# design.net
KiCad netlist of a schematic drawn in Altium Designer
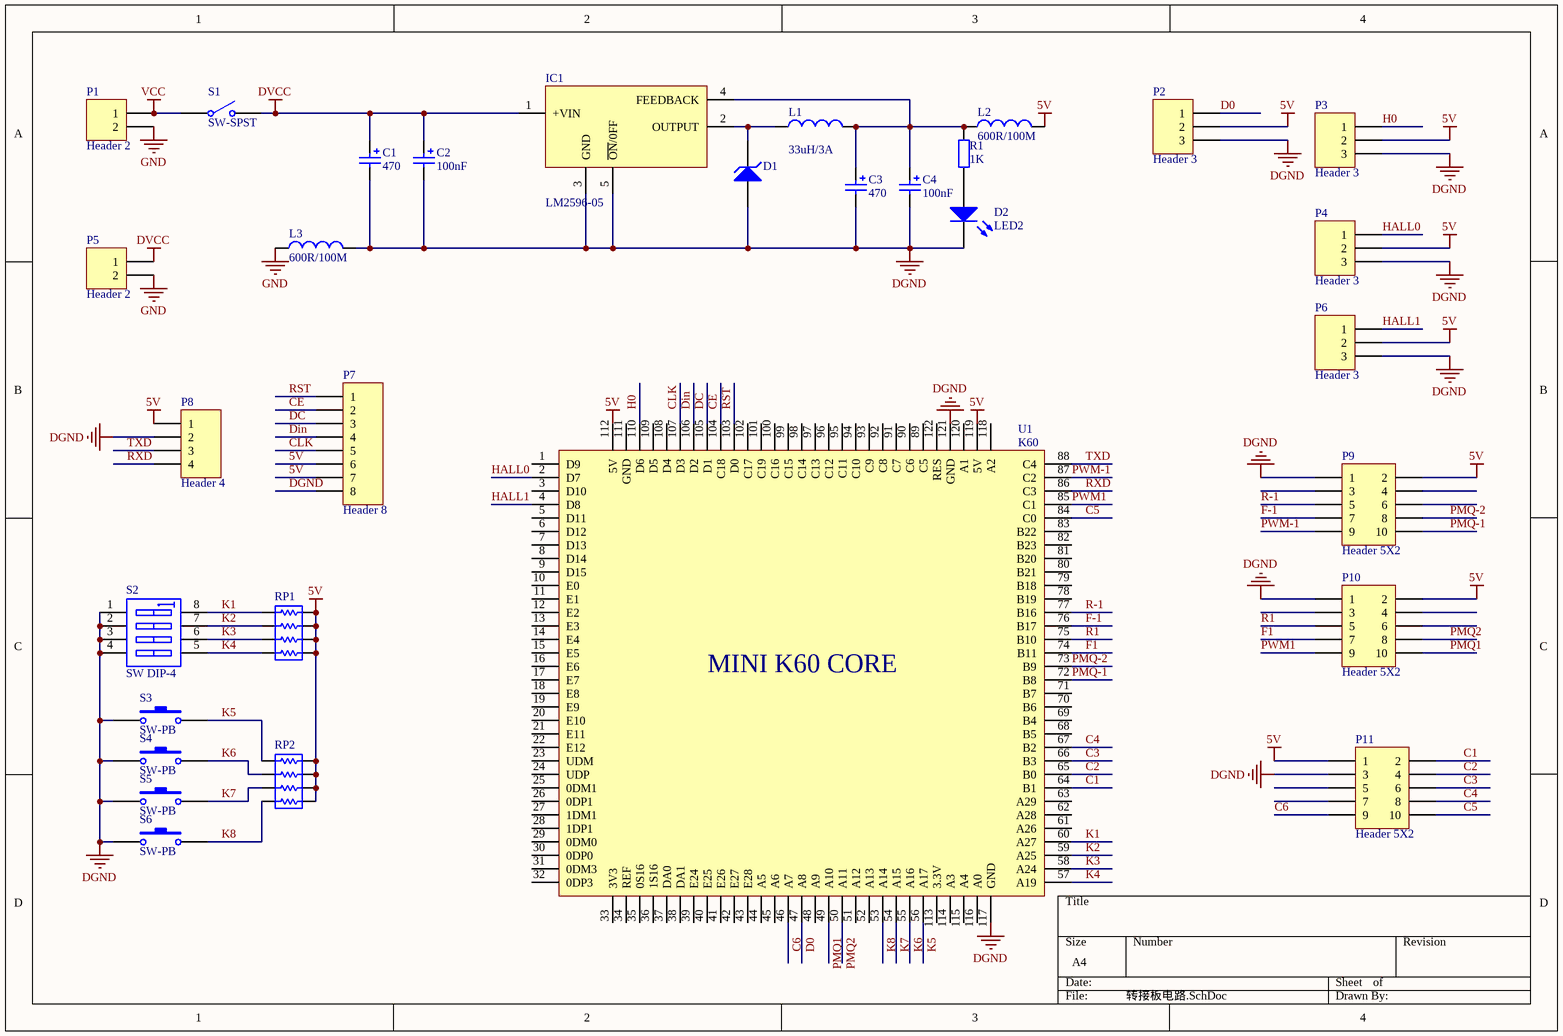
[diagram p0: 转接板电路.SchDoc]

(export (version "E")
  (design (tool "Eeschema 10.0.6"))
  (components
    (comp (ref "C1")
      (value "470")
      (footprint "ccc")
      (description "Polarized Capacitor (Axial)")
      (fields (field (name "PUBLISHER") "Altium Limited"))
      (libsource (lib "Miscellaneous Devices") (part "Cap Pol2"))
    )
    (comp (ref "C2")
      (value "100nF")
      (footprint "C0805")
      (description "Polarized Capacitor (Axial)")
      (fields (field (name "PUBLISHER") "Altium Limited"))
      (libsource (lib "Miscellaneous Devices") (part "Cap Pol2"))
    )
    (comp (ref "C3")
      (value "470")
      (footprint "ccc")
      (description "Polarized Capacitor (Axial)")
      (fields (field (name "PUBLISHER") "Altium Limited"))
      (libsource (lib "Miscellaneous Devices") (part "Cap Pol2"))
    )
    (comp (ref "C4")
      (value "100nF")
      (footprint "C0805")
      (description "Polarized Capacitor (Axial)")
      (fields (field (name "PUBLISHER") "Altium Limited"))
      (libsource (lib "Miscellaneous Devices") (part "Cap Pol2"))
    )
    (comp (ref "D1")
      (value "D Zener")
      (footprint "D1810")
      (description "Zener Diode")
      (fields (field (name "PUBLISHER") "Altium Limited"))
      (libsource (lib "Miscellaneous Devices") (part "D Zener"))
    )
    (comp (ref "D2")
      (value "LED2")
      (footprint "D0805")
      (description "Typical RED, GREEN, YELLOW, AMBER GaAs LED")
      (fields (field (name "PUBLISHER") "Altium Limited"))
      (libsource (lib "Miscellaneous Devices") (part "LED2"))
    )
    (comp (ref "IC1")
      (value "LM2596-05")
      (footprint "TO-263-5")
      (libsource (lib "飞思卡尔元件库") (part "LM2596-05"))
    )
    (comp (ref "L1")
      (value "33uH/3A")
      (footprint "L-12*12MM-S")
      (description "Inductor")
      (fields (field (name "PUBLISHER") "Altium Limited"))
      (libsource (lib "Miscellaneous Devices") (part "Inductor"))
    )
    (comp (ref "L2")
      (value "600R/100M")
      (footprint "L1206")
      (description "Inductor")
      (fields (field (name "PUBLISHER") "Altium Limited"))
      (libsource (lib "Miscellaneous Devices") (part "Inductor"))
    )
    (comp (ref "L3")
      (value "600R/100M")
      (footprint "L1206")
      (description "Inductor")
      (fields (field (name "PUBLISHER") "Altium Limited"))
      (libsource (lib "Miscellaneous Devices") (part "Inductor"))
    )
    (comp (ref "P1")
      (value "Header 2")
      (footprint "SIP2-1")
      (description "Header, 2-Pin")
      (fields (field (name "PUBLISHER") "Altium Limited"))
      (libsource (lib "Miscellaneous Connectors") (part "Header 2"))
    )
    (comp (ref "P2")
      (value "Header 3")
      (footprint "SIP3")
      (description "Header, 3-Pin")
      (fields (field (name "PUBLISHER") "Altium Limited"))
      (libsource (lib "Miscellaneous Connectors") (part "Header 3"))
    )
    (comp (ref "P3")
      (value "Header 3")
      (footprint "SIP3")
      (description "Header, 3-Pin")
      (fields (field (name "PUBLISHER") "Altium Limited"))
      (libsource (lib "Miscellaneous Connectors") (part "Header 3"))
    )
    (comp (ref "P4")
      (value "Header 3")
      (footprint "SIP3")
      (description "Header, 3-Pin")
      (fields (field (name "PUBLISHER") "Altium Limited"))
      (libsource (lib "Miscellaneous Connectors") (part "Header 3"))
    )
    (comp (ref "P5")
      (value "Header 2")
      (footprint "SIP2-1")
      (description "Header, 2-Pin")
      (fields (field (name "PUBLISHER") "Altium Limited"))
      (libsource (lib "Miscellaneous Connectors") (part "Header 2"))
    )
    (comp (ref "P6")
      (value "Header 3")
      (footprint "SIP3")
      (description "Header, 3-Pin")
      (fields (field (name "PUBLISHER") "Altium Limited"))
      (libsource (lib "Miscellaneous Connectors") (part "Header 3"))
    )
    (comp (ref "P7")
      (value "Header 8")
      (footprint "SIP8")
      (description "Header, 8-Pin")
      (fields (field (name "PUBLISHER") "Altium Limited"))
      (libsource (lib "Miscellaneous Connectors") (part "Header 8"))
    )
    (comp (ref "P8")
      (value "Header 4")
      (footprint "SIP4")
      (description "Header, 4-Pin")
      (fields (field (name "PUBLISHER") "Altium Limited"))
      (libsource (lib "Miscellaneous Connectors") (part "Header 4"))
    )
    (comp (ref "P9")
      (value "Header 5X2")
      (footprint "SIP10")
      (description "Header, 5-Pin, Dual row")
      (fields (field (name "PUBLISHER") "Altium Limited"))
      (libsource (lib "Miscellaneous Connectors") (part "Header 5X2"))
    )
    (comp (ref "P10")
      (value "Header 5X2")
      (footprint "SIP10")
      (description "Header, 5-Pin, Dual row")
      (fields (field (name "PUBLISHER") "Altium Limited"))
      (libsource (lib "Miscellaneous Connectors") (part "Header 5X2"))
    )
    (comp (ref "P11")
      (value "Header 5X2")
      (footprint "SIP10")
      (description "Header, 5-Pin, Dual row")
      (fields (field (name "PUBLISHER") "Altium Limited"))
      (libsource (lib "Miscellaneous Connectors") (part "Header 5X2"))
    )
    (comp (ref "R1")
      (value "1K")
      (footprint "R0805")
      (description "Resistor")
      (fields (field (name "Comment") "Res2") (field (name "PUBLISHER") "Altium Limited"))
      (libsource (lib "Miscellaneous Devices") (part "Res2"))
    )
    (comp (ref "RP1")
      (value "R  PAIZU")
      (footprint "8P4R-0805")
      (fields (field (name "PUBLISHER") "Altium Limited"))
      (libsource (lib "飞思卡尔元件库") (part "R  PAIZU"))
    )
    (comp (ref "RP2")
      (value "R  PAIZU")
      (footprint "8P4R-0805")
      (fields (field (name "PUBLISHER") "Altium Limited"))
      (libsource (lib "飞思卡尔元件库") (part "R  PAIZU"))
    )
    (comp (ref "S1")
      (value "SW-SPST")
      (footprint "PCBComponent_1")
      (description "Single-Pole, Single-Throw Switch")
      (fields (field (name "PUBLISHER") "Altium Limited"))
      (libsource (lib "Miscellaneous Devices") (part "SW-SPST"))
    )
    (comp (ref "S2")
      (value "SW DIP-4")
      (footprint "BM-SW-4")
      (description "DIP Switch, 4 Position, SPST")
      (fields (field (name "PUBLISHER") "Altium Limited"))
      (libsource (lib "Miscellaneous Devices") (part "SW DIP-4"))
    )
    (comp (ref "S3")
      (value "SW-PB")
      (footprint "SW-SMD1")
      (description "Switch")
      (fields (field (name "PUBLISHER") "Altium Limited"))
      (libsource (lib "Miscellaneous Devices") (part "SW-PB"))
    )
    (comp (ref "S4")
      (value "SW-PB")
      (footprint "SW-SMD1")
      (description "Switch")
      (fields (field (name "PUBLISHER") "Altium Limited"))
      (libsource (lib "Miscellaneous Devices") (part "SW-PB"))
    )
    (comp (ref "S5")
      (value "SW-PB")
      (footprint "SW-SMD1")
      (description "Switch")
      (fields (field (name "PUBLISHER") "Altium Limited"))
      (libsource (lib "Miscellaneous Devices") (part "SW-PB"))
    )
    (comp (ref "S6")
      (value "SW-PB")
      (footprint "SW-SMD1")
      (description "Switch")
      (fields (field (name "PUBLISHER") "Altium Limited"))
      (libsource (lib "Miscellaneous Devices") (part "SW-PB"))
    )
    (comp (ref "U1") (value "K60") (footprint "K60-MK") (libsource (lib "飞思卡尔元件库") (part "K60")))
  )
  (nets
    (net (code "1") (name "/C1") (class "Default")
      (node (ref "P11") (pin "2") (pinfunction "2_2") (pintype "passive"))
      (node (ref "U1") (pin "64") (pinfunction "B1_64") (pintype "passive"))
    )
    (net (code "2") (name "/C2") (class "Default")
      (node (ref "P11") (pin "4") (pinfunction "4_4") (pintype "passive"))
      (node (ref "U1") (pin "65") (pinfunction "B0_65") (pintype "passive"))
    )
    (net (code "3") (name "/C3") (class "Default")
      (node (ref "P11") (pin "6") (pinfunction "6_6") (pintype "passive"))
      (node (ref "U1") (pin "66") (pinfunction "B3_66") (pintype "passive"))
    )
    (net (code "4") (name "/C4") (class "Default")
      (node (ref "P11") (pin "8") (pinfunction "8_8") (pintype "passive"))
      (node (ref "U1") (pin "67") (pinfunction "B2_67") (pintype "passive"))
    )
    (net (code "5") (name "/C5") (class "Default")
      (node (ref "P11") (pin "10") (pinfunction "10_10") (pintype "passive"))
      (node (ref "U1") (pin "84") (pinfunction "C0_84") (pintype "passive"))
    )
    (net (code "6") (name "/C6") (class "Default")
      (node (ref "P11") (pin "9") (pinfunction "9_9") (pintype "passive"))
      (node (ref "U1") (pin "46") (pinfunction "A7_46") (pintype "passive"))
    )
    (net (code "7") (name "/CE") (class "Default")
      (node (ref "P7") (pin "2") (pinfunction "2_2") (pintype "passive"))
      (node (ref "U1") (pin "104") (pinfunction "C18_104") (pintype "passive"))
    )
    (net (code "8") (name "/CLK") (class "Default")
      (node (ref "P7") (pin "5") (pinfunction "5_5") (pintype "passive"))
      (node (ref "U1") (pin "107") (pinfunction "D3_107") (pintype "passive"))
    )
    (net (code "9") (name "/D0") (class "Default")
      (node (ref "P2") (pin "1") (pinfunction "1_1") (pintype "passive"))
      (node (ref "U1") (pin "47") (pinfunction "A8_47") (pintype "passive"))
    )
    (net (code "10") (name "/DC") (class "Default")
      (node (ref "P7") (pin "3") (pinfunction "3_3") (pintype "passive"))
      (node (ref "U1") (pin "105") (pinfunction "D1_105") (pintype "passive"))
    )
    (net (code "11") (name "/Din") (class "Default")
      (node (ref "P7") (pin "4") (pinfunction "4_4") (pintype "passive"))
      (node (ref "U1") (pin "106") (pinfunction "D2_106") (pintype "passive"))
    )
    (net (code "12") (name "/F-1") (class "Default")
      (node (ref "P9") (pin "7") (pinfunction "7_7") (pintype "passive"))
      (node (ref "U1") (pin "76") (pinfunction "B17_76") (pintype "passive"))
    )
    (net (code "13") (name "/F1") (class "Default")
      (node (ref "P10") (pin "7") (pinfunction "7_7") (pintype "passive"))
      (node (ref "U1") (pin "74") (pinfunction "B11_74") (pintype "passive"))
    )
    (net (code "14") (name "/H0") (class "Default")
      (node (ref "P3") (pin "1") (pinfunction "1_1") (pintype "passive"))
      (node (ref "U1") (pin "110") (pinfunction "D6_110") (pintype "passive"))
    )
    (net (code "15") (name "/HALL0") (class "Default")
      (node (ref "P4") (pin "1") (pinfunction "1_1") (pintype "passive"))
      (node (ref "U1") (pin "2") (pinfunction "D7_2") (pintype "passive"))
    )
    (net (code "16") (name "/HALL1") (class "Default")
      (node (ref "P6") (pin "1") (pinfunction "1_1") (pintype "passive"))
      (node (ref "U1") (pin "4") (pinfunction "D8_4") (pintype "passive"))
    )
    (net (code "17") (name "/K1") (class "Default")
      (node (ref "RP1") (pin "1") (pinfunction "1_1") (pintype "passive"))
      (node (ref "S2") (pin "8") (pinfunction "B1_8") (pintype "passive"))
      (node (ref "U1") (pin "60") (pinfunction "A27_60") (pintype "passive"))
    )
    (net (code "18") (name "/K2") (class "Default")
      (node (ref "RP1") (pin "2") (pinfunction "2_2") (pintype "passive"))
      (node (ref "S2") (pin "7") (pinfunction "B2_7") (pintype "passive"))
      (node (ref "U1") (pin "59") (pinfunction "A25_59") (pintype "passive"))
    )
    (net (code "19") (name "/K3") (class "Default")
      (node (ref "RP1") (pin "3") (pinfunction "3_3") (pintype "passive"))
      (node (ref "S2") (pin "6") (pinfunction "B3_6") (pintype "passive"))
      (node (ref "U1") (pin "58") (pinfunction "A24_58") (pintype "passive"))
    )
    (net (code "20") (name "/K4") (class "Default")
      (node (ref "RP1") (pin "4") (pinfunction "4_4") (pintype "passive"))
      (node (ref "S2") (pin "5") (pinfunction "B4_5") (pintype "passive"))
      (node (ref "U1") (pin "57") (pinfunction "A19_57") (pintype "passive"))
    )
    (net (code "21") (name "/K5") (class "Default")
      (node (ref "RP2") (pin "1") (pinfunction "1_1") (pintype "passive"))
      (node (ref "S3") (pin "2") (pinfunction "2_2") (pintype "passive"))
      (node (ref "U1") (pin "56") (pinfunction "A17_56") (pintype "passive"))
    )
    (net (code "22") (name "/K6") (class "Default")
      (node (ref "RP2") (pin "2") (pinfunction "2_2") (pintype "passive"))
      (node (ref "S4") (pin "2") (pinfunction "2_2") (pintype "passive"))
      (node (ref "U1") (pin "55") (pinfunction "A16_55") (pintype "passive"))
    )
    (net (code "23") (name "/K7") (class "Default")
      (node (ref "RP2") (pin "3") (pinfunction "3_3") (pintype "passive"))
      (node (ref "S5") (pin "2") (pinfunction "2_2") (pintype "passive"))
      (node (ref "U1") (pin "54") (pinfunction "A15_54") (pintype "passive"))
    )
    (net (code "24") (name "/K8") (class "Default")
      (node (ref "RP2") (pin "4") (pinfunction "4_4") (pintype "passive"))
      (node (ref "S6") (pin "2") (pinfunction "2_2") (pintype "passive"))
      (node (ref "U1") (pin "53") (pinfunction "A14_53") (pintype "passive"))
    )
    (net (code "25") (name "/PMQ-1") (class "Default")
      (node (ref "P9") (pin "10") (pinfunction "10_10") (pintype "passive"))
      (node (ref "U1") (pin "72") (pinfunction "B8_72") (pintype "passive"))
    )
    (net (code "26") (name "/PMQ-2") (class "Default")
      (node (ref "P9") (pin "8") (pinfunction "8_8") (pintype "passive"))
      (node (ref "U1") (pin "73") (pinfunction "B9_73") (pintype "passive"))
    )
    (net (code "27") (name "/PMQ1") (class "Default")
      (node (ref "P10") (pin "10") (pinfunction "10_10") (pintype "passive"))
      (node (ref "U1") (pin "49") (pinfunction "A10_49") (pintype "passive"))
    )
    (net (code "28") (name "/PMQ2") (class "Default")
      (node (ref "P10") (pin "8") (pinfunction "8_8") (pintype "passive"))
      (node (ref "U1") (pin "50") (pinfunction "A11_50") (pintype "passive"))
    )
    (net (code "29") (name "/PWM-1") (class "Default")
      (node (ref "P9") (pin "9") (pinfunction "9_9") (pintype "passive"))
      (node (ref "U1") (pin "87") (pinfunction "C2_87") (pintype "passive"))
    )
    (net (code "30") (name "/PWM1") (class "Default")
      (node (ref "P10") (pin "9") (pinfunction "9_9") (pintype "passive"))
      (node (ref "U1") (pin "85") (pinfunction "C1_85") (pintype "passive"))
    )
    (net (code "31") (name "/R-1") (class "Default")
      (node (ref "P9") (pin "5") (pinfunction "5_5") (pintype "passive"))
      (node (ref "U1") (pin "77") (pinfunction "B16_77") (pintype "passive"))
    )
    (net (code "32") (name "/R1") (class "Default")
      (node (ref "P10") (pin "5") (pinfunction "5_5") (pintype "passive"))
      (node (ref "U1") (pin "75") (pinfunction "B10_75") (pintype "passive"))
    )
    (net (code "33") (name "/RST") (class "Default")
      (node (ref "P7") (pin "1") (pinfunction "1_1") (pintype "passive"))
      (node (ref "U1") (pin "103") (pinfunction "D0_103") (pintype "passive"))
    )
    (net (code "34") (name "/RXD") (class "Default")
      (node (ref "P8") (pin "4") (pinfunction "4_4") (pintype "passive"))
      (node (ref "U1") (pin "86") (pinfunction "C3_86") (pintype "passive"))
    )
    (net (code "35") (name "/TXD") (class "Default")
      (node (ref "P8") (pin "3") (pinfunction "3_3") (pintype "passive"))
      (node (ref "U1") (pin "88") (pinfunction "C4_88") (pintype "passive"))
    )
    (net (code "36") (name "5V") (class "Default")
      (node (ref "L2") (pin "2") (pinfunction "2_2") (pintype "passive"))
      (node (ref "P10") (pin "2") (pinfunction "2_2") (pintype "passive"))
      (node (ref "P11") (pin "1") (pinfunction "1_1") (pintype "passive"))
      (node (ref "P2") (pin "2") (pinfunction "2_2") (pintype "passive"))
      (node (ref "P3") (pin "2") (pinfunction "2_2") (pintype "passive"))
      (node (ref "P4") (pin "2") (pinfunction "2_2") (pintype "passive"))
      (node (ref "P6") (pin "2") (pinfunction "2_2") (pintype "passive"))
      (node (ref "P7") (pin "6") (pinfunction "6_6") (pintype "passive"))
      (node (ref "P7") (pin "7") (pinfunction "7_7") (pintype "passive"))
      (node (ref "P8") (pin "1") (pinfunction "1_1") (pintype "passive"))
      (node (ref "P9") (pin "2") (pinfunction "2_2") (pintype "passive"))
      (node (ref "RP1") (pin "5") (pinfunction "5_5") (pintype "passive"))
      (node (ref "RP1") (pin "6") (pinfunction "6_6") (pintype "passive"))
      (node (ref "RP1") (pin "7") (pinfunction "7_7") (pintype "passive"))
      (node (ref "RP1") (pin "8") (pinfunction "8_8") (pintype "passive"))
      (node (ref "RP2") (pin "5") (pinfunction "5_5") (pintype "passive"))
      (node (ref "RP2") (pin "6") (pinfunction "6_6") (pintype "passive"))
      (node (ref "RP2") (pin "7") (pinfunction "7_7") (pintype "passive"))
      (node (ref "RP2") (pin "8") (pinfunction "8_8") (pintype "passive"))
      (node (ref "U1") (pin "112") (pinfunction "5V_112") (pintype "passive"))
      (node (ref "U1") (pin "119") (pinfunction "5V_119") (pintype "passive"))
    )
    (net (code "37") (name "DGND") (class "Default")
      (node (ref "C1") (pin "2") (pinfunction "2_2") (pintype "passive"))
      (node (ref "C2") (pin "2") (pinfunction "2_2") (pintype "passive"))
      (node (ref "C3") (pin "2") (pinfunction "2_2") (pintype "passive"))
      (node (ref "C4") (pin "2") (pinfunction "2_2") (pintype "passive"))
      (node (ref "D1") (pin "1") (pinfunction "A_1") (pintype "passive"))
      (node (ref "D2") (pin "2") (pinfunction "K_2") (pintype "passive"))
      (node (ref "IC1") (pin "3") (pinfunction "GND_3") (pintype "passive"))
      (node (ref "IC1") (pin "5") (pinfunction "~{ON}/0FF_5") (pintype "passive"))
      (node (ref "L3") (pin "2") (pinfunction "2_2") (pintype "passive"))
      (node (ref "P10") (pin "1") (pinfunction "1_1") (pintype "passive"))
      (node (ref "P11") (pin "3") (pinfunction "3_3") (pintype "passive"))
      (node (ref "P2") (pin "3") (pinfunction "3_3") (pintype "passive"))
      (node (ref "P3") (pin "3") (pinfunction "3_3") (pintype "passive"))
      (node (ref "P4") (pin "3") (pinfunction "3_3") (pintype "passive"))
      (node (ref "P6") (pin "3") (pinfunction "3_3") (pintype "passive"))
      (node (ref "P7") (pin "8") (pinfunction "8_8") (pintype "passive"))
      (node (ref "P8") (pin "2") (pinfunction "2_2") (pintype "passive"))
      (node (ref "P9") (pin "1") (pinfunction "1_1") (pintype "passive"))
      (node (ref "S2") (pin "1") (pinfunction "A1_1") (pintype "passive"))
      (node (ref "S2") (pin "2") (pinfunction "A2_2") (pintype "passive"))
      (node (ref "S2") (pin "3") (pinfunction "A3_3") (pintype "passive"))
      (node (ref "S2") (pin "4") (pinfunction "A4_4") (pintype "passive"))
      (node (ref "S3") (pin "1") (pinfunction "1_1") (pintype "passive"))
      (node (ref "S4") (pin "1") (pinfunction "1_1") (pintype "passive"))
      (node (ref "S5") (pin "1") (pinfunction "1_1") (pintype "passive"))
      (node (ref "S6") (pin "1") (pinfunction "1_1") (pintype "passive"))
      (node (ref "U1") (pin "117") (pinfunction "GND_117") (pintype "passive"))
      (node (ref "U1") (pin "121") (pinfunction "GND_121") (pintype "passive"))
    )
    (net (code "38") (name "DVCC") (class "Default")
      (node (ref "C1") (pin "1") (pinfunction "1_1") (pintype "passive"))
      (node (ref "C2") (pin "1") (pinfunction "1_1") (pintype "passive"))
      (node (ref "IC1") (pin "1") (pinfunction "+VIN_1") (pintype "passive"))
      (node (ref "P5") (pin "1") (pinfunction "1_1") (pintype "passive"))
      (node (ref "S1") (pin "2") (pinfunction "NO_2") (pintype "passive"))
    )
    (net (code "39") (name "GND") (class "Default")
      (node (ref "L3") (pin "1") (pinfunction "1_1") (pintype "passive"))
      (node (ref "P1") (pin "2") (pinfunction "2_2") (pintype "passive"))
      (node (ref "P5") (pin "2") (pinfunction "2_2") (pintype "passive"))
    )
    (net (code "40") (name "Net-(D1-K)") (class "Default")
      (node (ref "D1") (pin "2") (pinfunction "K_2") (pintype "passive"))
      (node (ref "IC1") (pin "2") (pinfunction "OUTPUT_2") (pintype "passive"))
      (node (ref "L1") (pin "1") (pinfunction "1_1") (pintype "passive"))
    )
    (net (code "41") (name "Net-(D2-A)") (class "Default")
      (node (ref "D2") (pin "1") (pinfunction "A_1") (pintype "passive"))
      (node (ref "R1") (pin "2") (pinfunction "2_2") (pintype "passive"))
    )
    (net (code "42") (name "Net-(IC1-FEEDBACK)") (class "Default")
      (node (ref "C3") (pin "1") (pinfunction "1_1") (pintype "passive"))
      (node (ref "C4") (pin "1") (pinfunction "1_1") (pintype "passive"))
      (node (ref "IC1") (pin "4") (pinfunction "FEEDBACK_4") (pintype "passive"))
      (node (ref "L1") (pin "2") (pinfunction "2_2") (pintype "passive"))
      (node (ref "L2") (pin "1") (pinfunction "1_1") (pintype "passive"))
      (node (ref "R1") (pin "1") (pinfunction "1_1") (pintype "passive"))
    )
    (net (code "43") (name "VCC") (class "Default")
      (node (ref "P1") (pin "1") (pinfunction "1_1") (pintype "passive"))
      (node (ref "S1") (pin "1") (pinfunction "COMMON_1") (pintype "passive"))
    )
    (net (code "44") (name "unconnected-(P9-Pad3)") (class "Default")
      (node (ref "P9") (pin "3") (pinfunction "3_3") (pintype "passive"))
    )
    (net (code "45") (name "unconnected-(P9-Pad4)") (class "Default")
      (node (ref "P9") (pin "4") (pinfunction "4_4") (pintype "passive"))
    )
    (net (code "46") (name "unconnected-(P9-Pad6)") (class "Default")
      (node (ref "P9") (pin "6") (pinfunction "6_6") (pintype "passive"))
    )
    (net (code "47") (name "unconnected-(P10-Pad3)") (class "Default")
      (node (ref "P10") (pin "3") (pinfunction "3_3") (pintype "passive"))
    )
    (net (code "48") (name "unconnected-(P10-Pad4)") (class "Default")
      (node (ref "P10") (pin "4") (pinfunction "4_4") (pintype "passive"))
    )
    (net (code "49") (name "unconnected-(P10-Pad6)") (class "Default")
      (node (ref "P10") (pin "6") (pinfunction "6_6") (pintype "passive"))
    )
    (net (code "50") (name "unconnected-(P11-Pad5)") (class "Default")
      (node (ref "P11") (pin "5") (pinfunction "5_5") (pintype "passive"))
    )
    (net (code "51") (name "unconnected-(P11-Pad7)") (class "Default")
      (node (ref "P11") (pin "7") (pinfunction "7_7") (pintype "passive"))
    )
    (net (code "52") (name "unconnected-(U1-0DM0-Pad29)") (class "Default")
      (node (ref "U1") (pin "29") (pinfunction "0DM0_29") (pintype "passive"))
    )
    (net (code "53") (name "unconnected-(U1-0DM1-Pad25)") (class "Default")
      (node (ref "U1") (pin "25") (pinfunction "0DM1_25") (pintype "passive"))
    )
    (net (code "54") (name "unconnected-(U1-0DM3-Pad31)") (class "Default")
      (node (ref "U1") (pin "31") (pinfunction "0DM3_31") (pintype "passive"))
    )
    (net (code "55") (name "unconnected-(U1-0DP0-Pad30)") (class "Default")
      (node (ref "U1") (pin "30") (pinfunction "0DP0_30") (pintype "passive"))
    )
    (net (code "56") (name "unconnected-(U1-0DP1-Pad26)") (class "Default")
      (node (ref "U1") (pin "26") (pinfunction "0DP1_26") (pintype "passive"))
    )
    (net (code "57") (name "unconnected-(U1-0DP3-Pad32)") (class "Default")
      (node (ref "U1") (pin "32") (pinfunction "0DP3_32") (pintype "passive"))
    )
    (net (code "58") (name "unconnected-(U1-0S16-Pad35)") (class "Default")
      (node (ref "U1") (pin "35") (pinfunction "0S16_35") (pintype "passive"))
    )
    (net (code "59") (name "unconnected-(U1-1DM1-Pad27)") (class "Default")
      (node (ref "U1") (pin "27") (pinfunction "1DM1_27") (pintype "passive"))
    )
    (net (code "60") (name "unconnected-(U1-1DP1-Pad28)") (class "Default")
      (node (ref "U1") (pin "28") (pinfunction "1DP1_28") (pintype "passive"))
    )
    (net (code "61") (name "unconnected-(U1-1S16-Pad36)") (class "Default")
      (node (ref "U1") (pin "36") (pinfunction "1S16_36") (pintype "passive"))
    )
    (net (code "62") (name "unconnected-(U1-3.3V-Pad113)") (class "Default")
      (node (ref "U1") (pin "113") (pinfunction "3.3V_113") (pintype "passive"))
    )
    (net (code "63") (name "unconnected-(U1-3V3-Pad33)") (class "Default")
      (node (ref "U1") (pin "33") (pinfunction "3V3_33") (pintype "passive"))
    )
    (net (code "64") (name "unconnected-(U1-A0-Pad116)") (class "Default")
      (node (ref "U1") (pin "116") (pinfunction "A0_116") (pintype "passive"))
    )
    (net (code "65") (name "unconnected-(U1-A1-Pad120)") (class "Default")
      (node (ref "U1") (pin "120") (pinfunction "A1_120") (pintype "passive"))
    )
    (net (code "66") (name "unconnected-(U1-A2-Pad118)") (class "Default")
      (node (ref "U1") (pin "118") (pinfunction "A2_118") (pintype "passive"))
    )
    (net (code "67") (name "unconnected-(U1-A3-Pad114)") (class "Default")
      (node (ref "U1") (pin "114") (pinfunction "A3_114") (pintype "passive"))
    )
    (net (code "68") (name "unconnected-(U1-A4-Pad115)") (class "Default")
      (node (ref "U1") (pin "115") (pinfunction "A4_115") (pintype "passive"))
    )
    (net (code "69") (name "unconnected-(U1-A5-Pad44)") (class "Default")
      (node (ref "U1") (pin "44") (pinfunction "A5_44") (pintype "passive"))
    )
    (net (code "70") (name "unconnected-(U1-A6-Pad45)") (class "Default")
      (node (ref "U1") (pin "45") (pinfunction "A6_45") (pintype "passive"))
    )
    (net (code "71") (name "unconnected-(U1-A9-Pad48)") (class "Default")
      (node (ref "U1") (pin "48") (pinfunction "A9_48") (pintype "passive"))
    )
    (net (code "72") (name "unconnected-(U1-A12-Pad51)") (class "Default")
      (node (ref "U1") (pin "51") (pinfunction "A12_51") (pintype "passive"))
    )
    (net (code "73") (name "unconnected-(U1-A13-Pad52)") (class "Default")
      (node (ref "U1") (pin "52") (pinfunction "A13_52") (pintype "passive"))
    )
    (net (code "74") (name "unconnected-(U1-A26-Pad61)") (class "Default")
      (node (ref "U1") (pin "61") (pinfunction "A26_61") (pintype "passive"))
    )
    (net (code "75") (name "unconnected-(U1-A28-Pad62)") (class "Default")
      (node (ref "U1") (pin "62") (pinfunction "A28_62") (pintype "passive"))
    )
    (net (code "76") (name "unconnected-(U1-A29-Pad63)") (class "Default")
      (node (ref "U1") (pin "63") (pinfunction "A29_63") (pintype "passive"))
    )
    (net (code "77") (name "unconnected-(U1-B4-Pad69)") (class "Default")
      (node (ref "U1") (pin "69") (pinfunction "B4_69") (pintype "passive"))
    )
    (net (code "78") (name "unconnected-(U1-B5-Pad68)") (class "Default")
      (node (ref "U1") (pin "68") (pinfunction "B5_68") (pintype "passive"))
    )
    (net (code "79") (name "unconnected-(U1-B6-Pad70)") (class "Default")
      (node (ref "U1") (pin "70") (pinfunction "B6_70") (pintype "passive"))
    )
    (net (code "80") (name "unconnected-(U1-B7-Pad71)") (class "Default")
      (node (ref "U1") (pin "71") (pinfunction "B7_71") (pintype "passive"))
    )
    (net (code "81") (name "unconnected-(U1-B18-Pad79)") (class "Default")
      (node (ref "U1") (pin "79") (pinfunction "B18_79") (pintype "passive"))
    )
    (net (code "82") (name "unconnected-(U1-B19-Pad78)") (class "Default")
      (node (ref "U1") (pin "78") (pinfunction "B19_78") (pintype "passive"))
    )
    (net (code "83") (name "unconnected-(U1-B20-Pad81)") (class "Default")
      (node (ref "U1") (pin "81") (pinfunction "B20_81") (pintype "passive"))
    )
    (net (code "84") (name "unconnected-(U1-B21-Pad80)") (class "Default")
      (node (ref "U1") (pin "80") (pinfunction "B21_80") (pintype "passive"))
    )
    (net (code "85") (name "unconnected-(U1-B22-Pad83)") (class "Default")
      (node (ref "U1") (pin "83") (pinfunction "B22_83") (pintype "passive"))
    )
    (net (code "86") (name "unconnected-(U1-B23-Pad82)") (class "Default")
      (node (ref "U1") (pin "82") (pinfunction "B23_82") (pintype "passive"))
    )
    (net (code "87") (name "unconnected-(U1-C5-Pad89)") (class "Default")
      (node (ref "U1") (pin "89") (pinfunction "C5_89") (pintype "passive"))
    )
    (net (code "88") (name "unconnected-(U1-C6-Pad90)") (class "Default")
      (node (ref "U1") (pin "90") (pinfunction "C6_90") (pintype "passive"))
    )
    (net (code "89") (name "unconnected-(U1-C7-Pad91)") (class "Default")
      (node (ref "U1") (pin "91") (pinfunction "C7_91") (pintype "passive"))
    )
    (net (code "90") (name "unconnected-(U1-C8-Pad92)") (class "Default")
      (node (ref "U1") (pin "92") (pinfunction "C8_92") (pintype "passive"))
    )
    (net (code "91") (name "unconnected-(U1-C9-Pad93)") (class "Default")
      (node (ref "U1") (pin "93") (pinfunction "C9_93") (pintype "passive"))
    )
    (net (code "92") (name "unconnected-(U1-C10-Pad94)") (class "Default")
      (node (ref "U1") (pin "94") (pinfunction "C10_94") (pintype "passive"))
    )
    (net (code "93") (name "unconnected-(U1-C11-Pad95)") (class "Default")
      (node (ref "U1") (pin "95") (pinfunction "C11_95") (pintype "passive"))
    )
    (net (code "94") (name "unconnected-(U1-C12-Pad96)") (class "Default")
      (node (ref "U1") (pin "96") (pinfunction "C12_96") (pintype "passive"))
    )
    (net (code "95") (name "unconnected-(U1-C13-Pad97)") (class "Default")
      (node (ref "U1") (pin "97") (pinfunction "C13_97") (pintype "passive"))
    )
    (net (code "96") (name "unconnected-(U1-C14-Pad98)") (class "Default")
      (node (ref "U1") (pin "98") (pinfunction "C14_98") (pintype "passive"))
    )
    (net (code "97") (name "unconnected-(U1-C15-Pad99)") (class "Default")
      (node (ref "U1") (pin "99") (pinfunction "C15_99") (pintype "passive"))
    )
    (net (code "98") (name "unconnected-(U1-C16-Pad100)") (class "Default")
      (node (ref "U1") (pin "100") (pinfunction "C16_100") (pintype "passive"))
    )
    (net (code "99") (name "unconnected-(U1-C17-Pad102)") (class "Default")
      (node (ref "U1") (pin "102") (pinfunction "C17_102") (pintype "passive"))
    )
    (net (code "100") (name "unconnected-(U1-C19-Pad101)") (class "Default")
      (node (ref "U1") (pin "101") (pinfunction "C19_101") (pintype "passive"))
    )
    (net (code "101") (name "unconnected-(U1-D4-Pad108)") (class "Default")
      (node (ref "U1") (pin "108") (pinfunction "D4_108") (pintype "passive"))
    )
    (net (code "102") (name "unconnected-(U1-D5-Pad109)") (class "Default")
      (node (ref "U1") (pin "109") (pinfunction "D5_109") (pintype "passive"))
    )
    (net (code "103") (name "unconnected-(U1-D9-Pad1)") (class "Default")
      (node (ref "U1") (pin "1") (pinfunction "D9_1") (pintype "passive"))
    )
    (net (code "104") (name "unconnected-(U1-D10-Pad3)") (class "Default")
      (node (ref "U1") (pin "3") (pinfunction "D10_3") (pintype "passive"))
    )
    (net (code "105") (name "unconnected-(U1-D11-Pad5)") (class "Default")
      (node (ref "U1") (pin "5") (pinfunction "D11_5") (pintype "passive"))
    )
    (net (code "106") (name "unconnected-(U1-D12-Pad6)") (class "Default")
      (node (ref "U1") (pin "6") (pinfunction "D12_6") (pintype "passive"))
    )
    (net (code "107") (name "unconnected-(U1-D13-Pad7)") (class "Default")
      (node (ref "U1") (pin "7") (pinfunction "D13_7") (pintype "passive"))
    )
    (net (code "108") (name "unconnected-(U1-D14-Pad8)") (class "Default")
      (node (ref "U1") (pin "8") (pinfunction "D14_8") (pintype "passive"))
    )
    (net (code "109") (name "unconnected-(U1-D15-Pad9)") (class "Default")
      (node (ref "U1") (pin "9") (pinfunction "D15_9") (pintype "passive"))
    )
    (net (code "110") (name "unconnected-(U1-DA0-Pad37)") (class "Default")
      (node (ref "U1") (pin "37") (pinfunction "DA0_37") (pintype "passive"))
    )
    (net (code "111") (name "unconnected-(U1-DA1-Pad38)") (class "Default")
      (node (ref "U1") (pin "38") (pinfunction "DA1_38") (pintype "passive"))
    )
    (net (code "112") (name "unconnected-(U1-E0-Pad10)") (class "Default")
      (node (ref "U1") (pin "10") (pinfunction "E0_10") (pintype "passive"))
    )
    (net (code "113") (name "unconnected-(U1-E1-Pad11)") (class "Default")
      (node (ref "U1") (pin "11") (pinfunction "E1_11") (pintype "passive"))
    )
    (net (code "114") (name "unconnected-(U1-E2-Pad12)") (class "Default")
      (node (ref "U1") (pin "12") (pinfunction "E2_12") (pintype "passive"))
    )
    (net (code "115") (name "unconnected-(U1-E3-Pad13)") (class "Default")
      (node (ref "U1") (pin "13") (pinfunction "E3_13") (pintype "passive"))
    )
    (net (code "116") (name "unconnected-(U1-E4-Pad14)") (class "Default")
      (node (ref "U1") (pin "14") (pinfunction "E4_14") (pintype "passive"))
    )
    (net (code "117") (name "unconnected-(U1-E5-Pad15)") (class "Default")
      (node (ref "U1") (pin "15") (pinfunction "E5_15") (pintype "passive"))
    )
    (net (code "118") (name "unconnected-(U1-E6-Pad16)") (class "Default")
      (node (ref "U1") (pin "16") (pinfunction "E6_16") (pintype "passive"))
    )
    (net (code "119") (name "unconnected-(U1-E7-Pad17)") (class "Default")
      (node (ref "U1") (pin "17") (pinfunction "E7_17") (pintype "passive"))
    )
    (net (code "120") (name "unconnected-(U1-E8-Pad18)") (class "Default")
      (node (ref "U1") (pin "18") (pinfunction "E8_18") (pintype "passive"))
    )
    (net (code "121") (name "unconnected-(U1-E9-Pad19)") (class "Default")
      (node (ref "U1") (pin "19") (pinfunction "E9_19") (pintype "passive"))
    )
    (net (code "122") (name "unconnected-(U1-E10-Pad20)") (class "Default")
      (node (ref "U1") (pin "20") (pinfunction "E10_20") (pintype "passive"))
    )
    (net (code "123") (name "unconnected-(U1-E11-Pad21)") (class "Default")
      (node (ref "U1") (pin "21") (pinfunction "E11_21") (pintype "passive"))
    )
    (net (code "124") (name "unconnected-(U1-E12-Pad22)") (class "Default")
      (node (ref "U1") (pin "22") (pinfunction "E12_22") (pintype "passive"))
    )
    (net (code "125") (name "unconnected-(U1-E24-Pad39)") (class "Default")
      (node (ref "U1") (pin "39") (pinfunction "E24_39") (pintype "passive"))
    )
    (net (code "126") (name "unconnected-(U1-E25-Pad40)") (class "Default")
      (node (ref "U1") (pin "40") (pinfunction "E25_40") (pintype "passive"))
    )
    (net (code "127") (name "unconnected-(U1-E26-Pad41)") (class "Default")
      (node (ref "U1") (pin "41") (pinfunction "E26_41") (pintype "passive"))
    )
    (net (code "128") (name "unconnected-(U1-E27-Pad42)") (class "Default")
      (node (ref "U1") (pin "42") (pinfunction "E27_42") (pintype "passive"))
    )
    (net (code "129") (name "unconnected-(U1-E28-Pad43)") (class "Default")
      (node (ref "U1") (pin "43") (pinfunction "E28_43") (pintype "passive"))
    )
    (net (code "130") (name "unconnected-(U1-GND-Pad111)") (class "Default")
      (node (ref "U1") (pin "111") (pinfunction "GND_111") (pintype "passive"))
    )
    (net (code "131") (name "unconnected-(U1-REF-Pad34)") (class "Default")
      (node (ref "U1") (pin "34") (pinfunction "REF_34") (pintype "passive"))
    )
    (net (code "132") (name "unconnected-(U1-RES-Pad122)") (class "Default")
      (node (ref "U1") (pin "122") (pinfunction "RES_122") (pintype "passive"))
    )
    (net (code "133") (name "unconnected-(U1-UDM-Pad23)") (class "Default")
      (node (ref "U1") (pin "23") (pinfunction "UDM_23") (pintype "passive"))
    )
    (net (code "134") (name "unconnected-(U1-UDP-Pad24)") (class "Default")
      (node (ref "U1") (pin "24") (pinfunction "UDP_24") (pintype "passive"))
    )
  )
)
